# quantum_PSU_V3_0.net
KiCad netlist of a schematic drawn in EAGLE
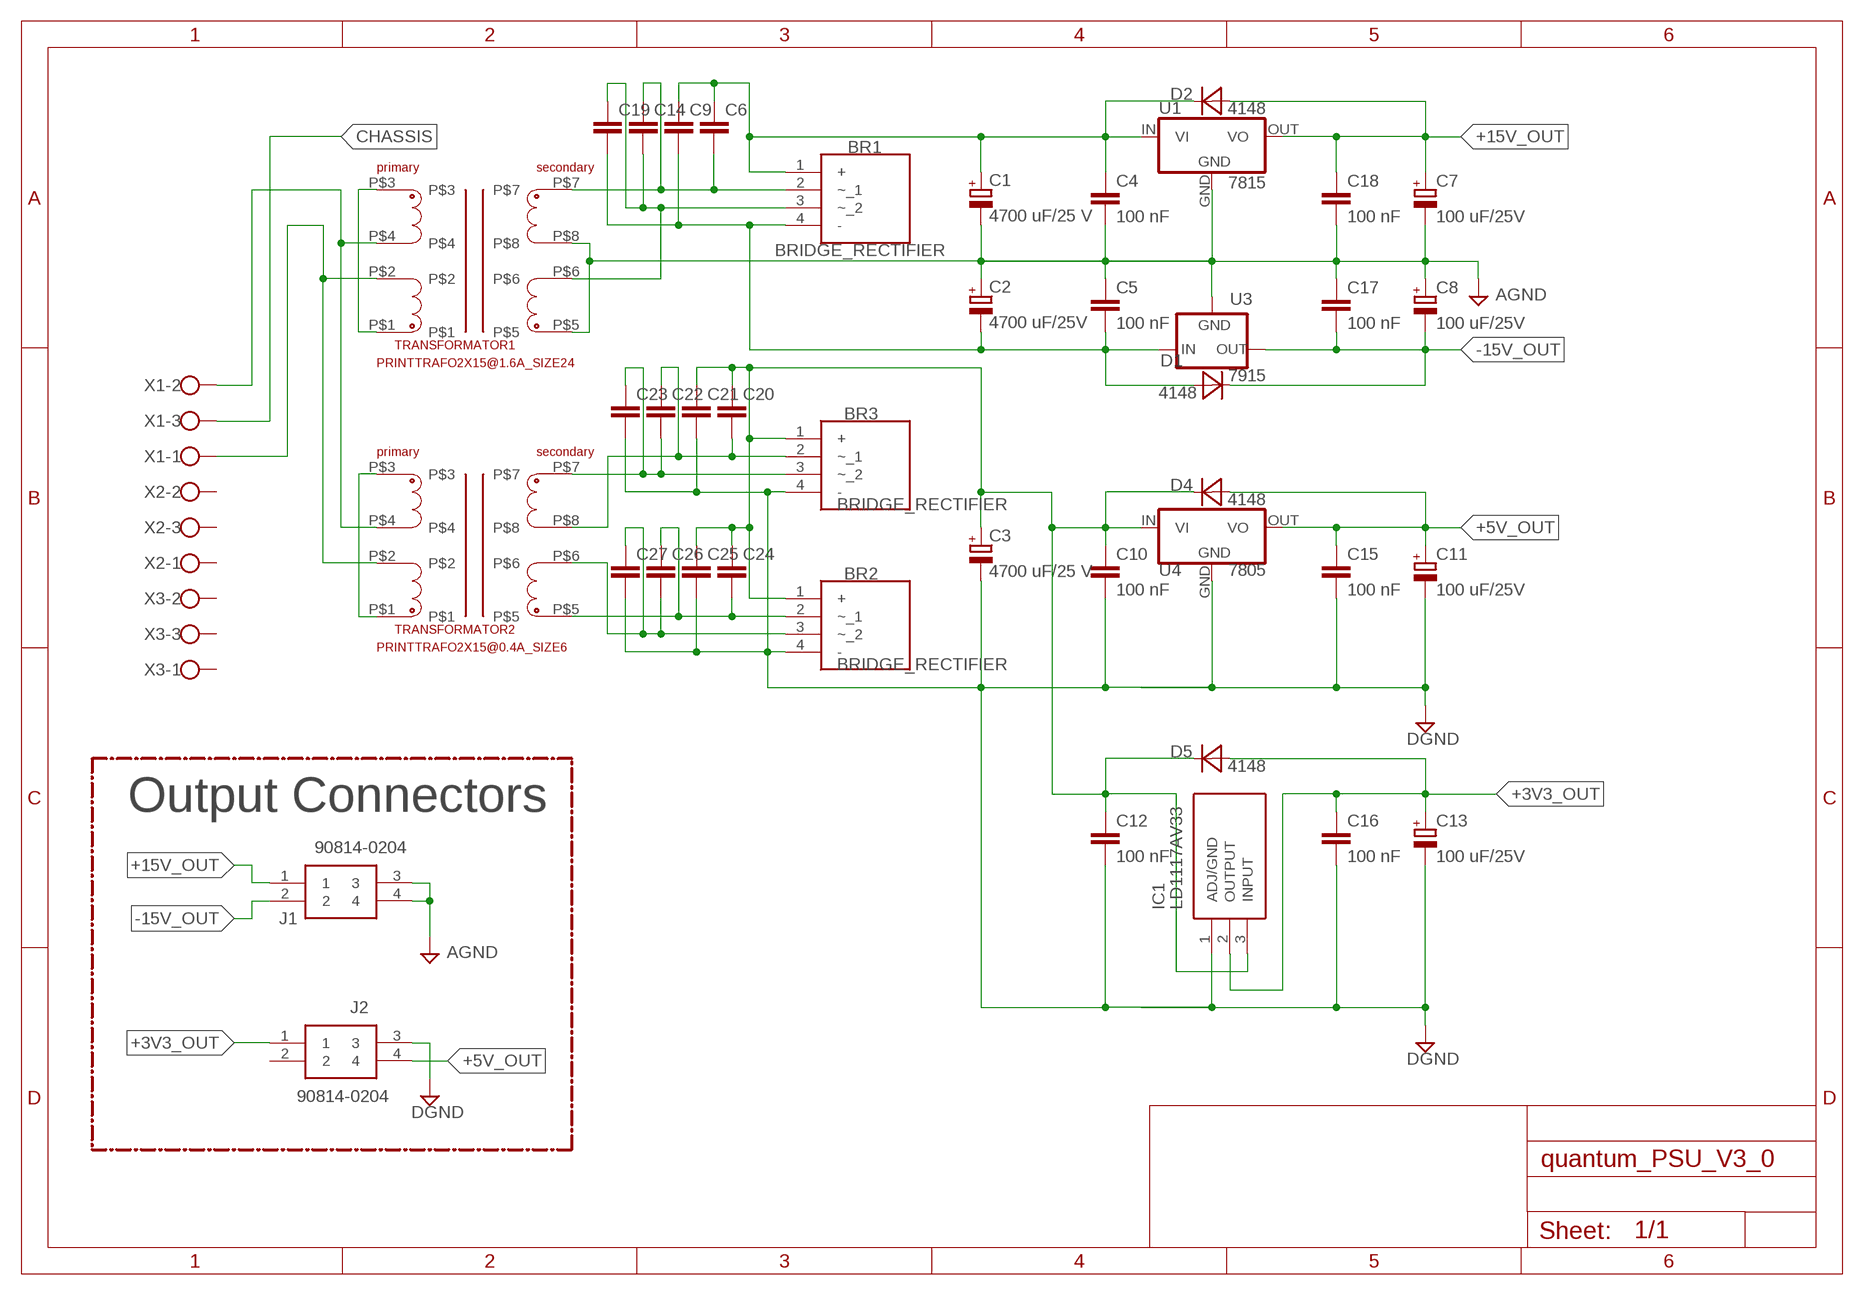
[diagram p0: schematic, sheet 1]

(export (version "E")
  (design (tool "Eeschema 10.0.6"))
  (components
    (comp (ref "BR1")
      (value "BRIDGE_RECTIFIER")
      (footprint "eagle-import:KBP308G")
      (fields
        (field (name "MANUFACTURER_PART_NUMBER") "KBP308G")
        (field (name "MOUSER_PART_NUMBER") "621-KBP308G")
      )
      (libsource (lib "eagle-import") (part "BRIDGE_RECTIFIER"))
    )
    (comp (ref "BR2")
      (value "BRIDGE_RECTIFIER")
      (footprint "eagle-import:KBP308G")
      (fields
        (field (name "MANUFACTURER_PART_NUMBER") "KBP308G")
        (field (name "MOUSER_PART_NUMBER") "621-KBP308G")
      )
      (libsource (lib "eagle-import") (part "BRIDGE_RECTIFIER"))
    )
    (comp (ref "BR3")
      (value "BRIDGE_RECTIFIER")
      (footprint "eagle-import:KBP308G")
      (fields
        (field (name "MANUFACTURER_PART_NUMBER") "KBP308G")
        (field (name "MOUSER_PART_NUMBER") "621-KBP308G")
      )
      (libsource (lib "eagle-import") (part "BRIDGE_RECTIFIER"))
    )
    (comp (ref "C1")
      (value "4700 uF/25 V")
      (footprint "eagle-import:ELECTROLYTIC_16MM")
      (libsource (lib "eagle-import") (part "CAPACITOR_ELECTROLYTIC_16MM-THT"))
    )
    (comp (ref "C2")
      (value "4700 uF/25V")
      (footprint "eagle-import:ELECTROLYTIC_16MM")
      (libsource (lib "eagle-import") (part "CAPACITOR_ELECTROLYTIC_16MM-THT"))
    )
    (comp (ref "C3")
      (value "4700 uF/25 V")
      (footprint "eagle-import:ELECTROLYTIC_16MM")
      (libsource (lib "eagle-import") (part "CAPACITOR_ELECTROLYTIC_16MM-THT"))
    )
    (comp (ref "C4")
      (value "100 nF")
      (footprint "eagle-import:C5MM")
      (libsource (lib "eagle-import") (part "CAPACITOR_5MM"))
    )
    (comp (ref "C5")
      (value "100 nF")
      (footprint "eagle-import:C5MM")
      (libsource (lib "eagle-import") (part "CAPACITOR_5MM"))
    )
    (comp (ref "C6")
      (value "CAPACITOR_2.5MM")
      (footprint "eagle-import:C2.5MM")
      (libsource (lib "eagle-import") (part "CAPACITOR_2.5MM"))
    )
    (comp (ref "C7")
      (value "100 uF/25V")
      (footprint "eagle-import:ELECTROLYTIC_8MM")
      (libsource (lib "eagle-import") (part "CAPACITOR_ELECTROLYTIC_8MM-THT"))
    )
    (comp (ref "C8")
      (value "100 uF/25V")
      (footprint "eagle-import:ELECTROLYTIC_8MM")
      (libsource (lib "eagle-import") (part "CAPACITOR_ELECTROLYTIC_8MM-THT"))
    )
    (comp (ref "C9")
      (value "CAPACITOR_2.5MM")
      (footprint "eagle-import:C2.5MM")
      (libsource (lib "eagle-import") (part "CAPACITOR_2.5MM"))
    )
    (comp (ref "C10")
      (value "100 nF")
      (footprint "eagle-import:C5MM")
      (libsource (lib "eagle-import") (part "CAPACITOR_5MM"))
    )
    (comp (ref "C11")
      (value "100 uF/25V")
      (footprint "eagle-import:ELECTROLYTIC_8MM")
      (libsource (lib "eagle-import") (part "CAPACITOR_ELECTROLYTIC_8MM-THT"))
    )
    (comp (ref "C12")
      (value "100 nF")
      (footprint "eagle-import:C5MM")
      (libsource (lib "eagle-import") (part "CAPACITOR_5MM"))
    )
    (comp (ref "C13")
      (value "100 uF/25V")
      (footprint "eagle-import:ELECTROLYTIC_8MM")
      (libsource (lib "eagle-import") (part "CAPACITOR_ELECTROLYTIC_8MM-THT"))
    )
    (comp (ref "C14")
      (value "CAPACITOR_2.5MM")
      (footprint "eagle-import:C2.5MM")
      (libsource (lib "eagle-import") (part "CAPACITOR_2.5MM"))
    )
    (comp (ref "C15")
      (value "100 nF")
      (footprint "eagle-import:C5MM")
      (libsource (lib "eagle-import") (part "CAPACITOR_5MM"))
    )
    (comp (ref "C16")
      (value "100 nF")
      (footprint "eagle-import:C5MM")
      (libsource (lib "eagle-import") (part "CAPACITOR_5MM"))
    )
    (comp (ref "C17")
      (value "100 nF")
      (footprint "eagle-import:C5MM")
      (libsource (lib "eagle-import") (part "CAPACITOR_5MM"))
    )
    (comp (ref "C18")
      (value "100 nF")
      (footprint "eagle-import:C5MM")
      (libsource (lib "eagle-import") (part "CAPACITOR_5MM"))
    )
    (comp (ref "C19")
      (value "CAPACITOR_2.5MM")
      (footprint "eagle-import:C2.5MM")
      (libsource (lib "eagle-import") (part "CAPACITOR_2.5MM"))
    )
    (comp (ref "C20")
      (value "CAPACITOR_2.5MM")
      (footprint "eagle-import:C2.5MM")
      (libsource (lib "eagle-import") (part "CAPACITOR_2.5MM"))
    )
    (comp (ref "C21")
      (value "CAPACITOR_2.5MM")
      (footprint "eagle-import:C2.5MM")
      (libsource (lib "eagle-import") (part "CAPACITOR_2.5MM"))
    )
    (comp (ref "C22")
      (value "CAPACITOR_2.5MM")
      (footprint "eagle-import:C2.5MM")
      (libsource (lib "eagle-import") (part "CAPACITOR_2.5MM"))
    )
    (comp (ref "C23")
      (value "CAPACITOR_2.5MM")
      (footprint "eagle-import:C2.5MM")
      (libsource (lib "eagle-import") (part "CAPACITOR_2.5MM"))
    )
    (comp (ref "C24")
      (value "CAPACITOR_2.5MM")
      (footprint "eagle-import:C2.5MM")
      (libsource (lib "eagle-import") (part "CAPACITOR_2.5MM"))
    )
    (comp (ref "C25")
      (value "CAPACITOR_2.5MM")
      (footprint "eagle-import:C2.5MM")
      (libsource (lib "eagle-import") (part "CAPACITOR_2.5MM"))
    )
    (comp (ref "C26")
      (value "CAPACITOR_2.5MM")
      (footprint "eagle-import:C2.5MM")
      (libsource (lib "eagle-import") (part "CAPACITOR_2.5MM"))
    )
    (comp (ref "C27")
      (value "CAPACITOR_2.5MM")
      (footprint "eagle-import:C2.5MM")
      (libsource (lib "eagle-import") (part "CAPACITOR_2.5MM"))
    )
    (comp (ref "D1")
      (value "4148")
      (footprint "eagle-import:DIODE_THT_STANDING")
      (fields (field (name "MOUSER_PART_NUMBER") "..."))
      (libsource (lib "eagle-import") (part "DIODE_4148_THT"))
    )
    (comp (ref "D2")
      (value "4148")
      (footprint "eagle-import:DIODE_THT_STANDING")
      (fields (field (name "MOUSER_PART_NUMBER") "..."))
      (libsource (lib "eagle-import") (part "DIODE_4148_THT"))
    )
    (comp (ref "D4")
      (value "4148")
      (footprint "eagle-import:DIODE_THT_STANDING")
      (fields (field (name "MOUSER_PART_NUMBER") "..."))
      (libsource (lib "eagle-import") (part "DIODE_4148_THT"))
    )
    (comp (ref "D5")
      (value "4148")
      (footprint "eagle-import:DIODE_THT_STANDING")
      (fields (field (name "MOUSER_PART_NUMBER") "..."))
      (libsource (lib "eagle-import") (part "DIODE_4148_THT"))
    )
    (comp (ref "IC1")
      (value "LD1117AV33")
      (footprint "eagle-import:TO255P460X1020X2008-3P")
      (fields (field (name "MOUSER_PART_NUMBER") "511-LD1117AV33"))
      (libsource (lib "eagle-import") (part "LD1117AV33"))
    )
    (comp (ref "J1")
      (value "90814-0204")
      (footprint "eagle-import:MOLEX_90814-0204")
      (fields (field (name "MOUSER_PART_NUMBER") "538-90814-0204"))
      (libsource (lib "eagle-import") (part "90814-0204"))
    )
    (comp (ref "J2")
      (value "90814-0204")
      (footprint "eagle-import:MOLEX_90814-0204")
      (fields (field (name "MOUSER_PART_NUMBER") "538-90814-0204"))
      (libsource (lib "eagle-import") (part "90814-0204"))
    )
    (comp (ref "TRANSFORMATOR1")
      (value "PRINTTRAFO2X15@1.6A_SIZE24")
      (footprint "eagle-import:LP_SIZE_24")
      (fields (field (name "MOUSER_PART_NUMBER") "530-LP-30-800"))
      (libsource (lib "eagle-import") (part "PRINTTRAFO_SIZE242X15@1.6A"))
    )
    (comp (ref "TRANSFORMATOR2")
      (value "PRINTTRAFO2X15@0.4A_SIZE6")
      (footprint "eagle-import:LP_SIZE_6")
      (fields (field (name "MOUSER_PART_NUMBER") "530-LP-30-200"))
      (libsource (lib "eagle-import") (part "PRINTTRAFO_SIZE62X15@0.4A"))
    )
    (comp (ref "U1")
      (value "7815")
      (footprint "eagle-import:78XXS_")
      (libsource (lib "eagle-import") (part "78_THT"))
    )
    (comp (ref "U3")
      (value "7915")
      (footprint "eagle-import:79XXS")
      (libsource (lib "eagle-import") (part "79_THT"))
    )
    (comp (ref "U4")
      (value "7805")
      (footprint "eagle-import:78XXS_")
      (libsource (lib "eagle-import") (part "78_THT"))
    )
    (comp (ref "X1")
      (value "CONNECTOR_3POL")
      (footprint "eagle-import:W237-103")
      (libsource (lib "eagle-import") (part "CONNECTOR_3POL"))
    )
    (comp (ref "X2")
      (value "CONNECTOR_3POL")
      (footprint "eagle-import:W237-103")
      (libsource (lib "eagle-import") (part "CONNECTOR_3POL"))
    )
    (comp (ref "X3")
      (value "CONNECTOR_3POL")
      (footprint "eagle-import:W237-103")
      (libsource (lib "eagle-import") (part "CONNECTOR_3POL"))
    )
  )
  (nets
    (net (code "1") (name "+3V3_OUT") (class "Default")
      (node (ref "C13") (pin "+") (pinfunction "+_+") (pintype "passive"))
      (node (ref "C16") (pin "1") (pinfunction "1_1") (pintype "passive"))
      (node (ref "D5") (pin "A") (pinfunction "A_A") (pintype "passive"))
      (node (ref "IC1") (pin "2") (pinfunction "OUTPUT_2") (pintype "bidirectional"))
      (node (ref "J2") (pin "1") (pinfunction "1_1") (pintype "bidirectional"))
    )
    (net (code "2") (name "+5V_OUT") (class "Default")
      (node (ref "C11") (pin "+") (pinfunction "+_+") (pintype "passive"))
      (node (ref "C15") (pin "1") (pinfunction "1_1") (pintype "passive"))
      (node (ref "D4") (pin "A") (pinfunction "A_A") (pintype "passive"))
      (node (ref "J2") (pin "4") (pinfunction "4_4") (pintype "bidirectional"))
      (node (ref "U4") (pin "OUT") (pinfunction "VO_OUT") (pintype "passive"))
    )
    (net (code "3") (name "+15V_OUT") (class "Default")
      (node (ref "C18") (pin "1") (pinfunction "1_1") (pintype "passive"))
      (node (ref "C7") (pin "+") (pinfunction "+_+") (pintype "passive"))
      (node (ref "D2") (pin "A") (pinfunction "A_A") (pintype "passive"))
      (node (ref "J1") (pin "1") (pinfunction "1_1") (pintype "bidirectional"))
      (node (ref "U1") (pin "OUT") (pinfunction "VO_OUT") (pintype "passive"))
    )
    (net (code "4") (name "-15V_OUT") (class "Default")
      (node (ref "C17") (pin "2") (pinfunction "2_2") (pintype "passive"))
      (node (ref "C8") (pin "-") (pinfunction "-_-") (pintype "passive"))
      (node (ref "D1") (pin "C") (pinfunction "C_C") (pintype "passive"))
      (node (ref "J1") (pin "2") (pinfunction "2_2") (pintype "bidirectional"))
      (node (ref "U3") (pin "OUT") (pinfunction "OUT_OUT") (pintype "passive"))
    )
    (net (code "5") (name "AGND") (class "Default")
      (node (ref "C1") (pin "-") (pinfunction "-_-") (pintype "passive"))
      (node (ref "C17") (pin "1") (pinfunction "1_1") (pintype "passive"))
      (node (ref "C18") (pin "2") (pinfunction "2_2") (pintype "passive"))
      (node (ref "C2") (pin "+") (pinfunction "+_+") (pintype "passive"))
      (node (ref "C4") (pin "2") (pinfunction "2_2") (pintype "passive"))
      (node (ref "C5") (pin "1") (pinfunction "1_1") (pintype "passive"))
      (node (ref "C7") (pin "-") (pinfunction "-_-") (pintype "passive"))
      (node (ref "C8") (pin "+") (pinfunction "+_+") (pintype "passive"))
      (node (ref "J1") (pin "3") (pinfunction "3_3") (pintype "bidirectional"))
      (node (ref "J1") (pin "4") (pinfunction "4_4") (pintype "bidirectional"))
      (node (ref "TRANSFORMATOR1") (pin "P$5") (pinfunction "P$5_P$5") (pintype "bidirectional"))
      (node (ref "TRANSFORMATOR1") (pin "P$8") (pinfunction "P$8_P$8") (pintype "bidirectional"))
      (node (ref "U1") (pin "GND") (pinfunction "GND_GND") (pintype "passive"))
      (node (ref "U3") (pin "GND") (pinfunction "GND_GND") (pintype "input"))
    )
    (net (code "6") (name "CHASSIS") (class "Default")
      (node (ref "X1") (pin "3") (pinfunction "KL_3") (pintype "passive"))
    )
    (net (code "7") (name "DGND") (class "Default")
      (node (ref "BR2") (pin "4") (pinfunction "-_4") (pintype "bidirectional"))
      (node (ref "BR3") (pin "4") (pinfunction "-_4") (pintype "bidirectional"))
      (node (ref "C10") (pin "2") (pinfunction "2_2") (pintype "passive"))
      (node (ref "C11") (pin "-") (pinfunction "-_-") (pintype "passive"))
      (node (ref "C12") (pin "2") (pinfunction "2_2") (pintype "passive"))
      (node (ref "C13") (pin "-") (pinfunction "-_-") (pintype "passive"))
      (node (ref "C15") (pin "2") (pinfunction "2_2") (pintype "passive"))
      (node (ref "C16") (pin "2") (pinfunction "2_2") (pintype "passive"))
      (node (ref "C21") (pin "2") (pinfunction "2_2") (pintype "passive"))
      (node (ref "C23") (pin "2") (pinfunction "2_2") (pintype "passive"))
      (node (ref "C25") (pin "2") (pinfunction "2_2") (pintype "passive"))
      (node (ref "C27") (pin "2") (pinfunction "2_2") (pintype "passive"))
      (node (ref "C3") (pin "-") (pinfunction "-_-") (pintype "passive"))
      (node (ref "IC1") (pin "1") (pinfunction "ADJ/GND_1") (pintype "bidirectional"))
      (node (ref "J2") (pin "3") (pinfunction "3_3") (pintype "bidirectional"))
      (node (ref "U4") (pin "GND") (pinfunction "GND_GND") (pintype "passive"))
    )
    (net (code "8") (name "Net-(BR1-+)") (class "Default")
      (node (ref "BR1") (pin "1") (pinfunction "+_1") (pintype "bidirectional"))
      (node (ref "C1") (pin "+") (pinfunction "+_+") (pintype "passive"))
      (node (ref "C4") (pin "1") (pinfunction "1_1") (pintype "passive"))
      (node (ref "C6") (pin "1") (pinfunction "1_1") (pintype "passive"))
      (node (ref "C9") (pin "1") (pinfunction "1_1") (pintype "passive"))
      (node (ref "D2") (pin "C") (pinfunction "C_C") (pintype "passive"))
      (node (ref "U1") (pin "IN") (pinfunction "VI_IN") (pintype "input"))
    )
    (net (code "9") (name "Net-(BR1--)") (class "Default")
      (node (ref "BR1") (pin "4") (pinfunction "-_4") (pintype "bidirectional"))
      (node (ref "C19") (pin "2") (pinfunction "2_2") (pintype "passive"))
      (node (ref "C2") (pin "-") (pinfunction "-_-") (pintype "passive"))
      (node (ref "C5") (pin "2") (pinfunction "2_2") (pintype "passive"))
      (node (ref "C9") (pin "2") (pinfunction "2_2") (pintype "passive"))
      (node (ref "D1") (pin "A") (pinfunction "A_A") (pintype "passive"))
      (node (ref "U3") (pin "IN") (pinfunction "IN_IN") (pintype "input"))
    )
    (net (code "10") (name "Net-(BR1-~{_1})") (class "Default")
      (node (ref "BR1") (pin "2") (pinfunction "~{_1}_2") (pintype "bidirectional"))
      (node (ref "C14") (pin "1") (pinfunction "1_1") (pintype "passive"))
      (node (ref "C6") (pin "2") (pinfunction "2_2") (pintype "passive"))
      (node (ref "TRANSFORMATOR1") (pin "P$7") (pinfunction "P$7_P$7") (pintype "bidirectional"))
    )
    (net (code "11") (name "Net-(BR1-~{_2})") (class "Default")
      (node (ref "BR1") (pin "3") (pinfunction "~{_2}_3") (pintype "bidirectional"))
      (node (ref "C14") (pin "2") (pinfunction "2_2") (pintype "passive"))
      (node (ref "C19") (pin "1") (pinfunction "1_1") (pintype "passive"))
      (node (ref "TRANSFORMATOR1") (pin "P$6") (pinfunction "P$6_P$6") (pintype "bidirectional"))
    )
    (net (code "12") (name "Net-(BR2-+)") (class "Default")
      (node (ref "BR2") (pin "1") (pinfunction "+_1") (pintype "bidirectional"))
      (node (ref "BR3") (pin "1") (pinfunction "+_1") (pintype "bidirectional"))
      (node (ref "C10") (pin "1") (pinfunction "1_1") (pintype "passive"))
      (node (ref "C12") (pin "1") (pinfunction "1_1") (pintype "passive"))
      (node (ref "C20") (pin "1") (pinfunction "1_1") (pintype "passive"))
      (node (ref "C21") (pin "1") (pinfunction "1_1") (pintype "passive"))
      (node (ref "C24") (pin "1") (pinfunction "1_1") (pintype "passive"))
      (node (ref "C25") (pin "1") (pinfunction "1_1") (pintype "passive"))
      (node (ref "C3") (pin "+") (pinfunction "+_+") (pintype "passive"))
      (node (ref "D4") (pin "C") (pinfunction "C_C") (pintype "passive"))
      (node (ref "D5") (pin "C") (pinfunction "C_C") (pintype "passive"))
      (node (ref "IC1") (pin "3") (pinfunction "INPUT_3") (pintype "bidirectional"))
      (node (ref "U4") (pin "IN") (pinfunction "VI_IN") (pintype "input"))
    )
    (net (code "13") (name "Net-(BR2-~{_1})") (class "Default")
      (node (ref "BR2") (pin "2") (pinfunction "~{_1}_2") (pintype "bidirectional"))
      (node (ref "C24") (pin "2") (pinfunction "2_2") (pintype "passive"))
      (node (ref "C26") (pin "1") (pinfunction "1_1") (pintype "passive"))
      (node (ref "TRANSFORMATOR2") (pin "P$5") (pinfunction "P$5_P$5") (pintype "bidirectional"))
    )
    (net (code "14") (name "Net-(BR2-~{_2})") (class "Default")
      (node (ref "BR2") (pin "3") (pinfunction "~{_2}_3") (pintype "bidirectional"))
      (node (ref "C26") (pin "2") (pinfunction "2_2") (pintype "passive"))
      (node (ref "C27") (pin "1") (pinfunction "1_1") (pintype "passive"))
      (node (ref "TRANSFORMATOR2") (pin "P$6") (pinfunction "P$6_P$6") (pintype "bidirectional"))
    )
    (net (code "15") (name "Net-(BR3-~{_1})") (class "Default")
      (node (ref "BR3") (pin "2") (pinfunction "~{_1}_2") (pintype "bidirectional"))
      (node (ref "C20") (pin "2") (pinfunction "2_2") (pintype "passive"))
      (node (ref "C22") (pin "1") (pinfunction "1_1") (pintype "passive"))
      (node (ref "TRANSFORMATOR2") (pin "P$8") (pinfunction "P$8_P$8") (pintype "bidirectional"))
    )
    (net (code "16") (name "Net-(BR3-~{_2})") (class "Default")
      (node (ref "BR3") (pin "3") (pinfunction "~{_2}_3") (pintype "bidirectional"))
      (node (ref "C22") (pin "2") (pinfunction "2_2") (pintype "passive"))
      (node (ref "C23") (pin "1") (pinfunction "1_1") (pintype "passive"))
      (node (ref "TRANSFORMATOR2") (pin "P$7") (pinfunction "P$7_P$7") (pintype "bidirectional"))
    )
    (net (code "17") (name "Net-(TRANSFORMATOR1-PadP$1)") (class "Default")
      (node (ref "TRANSFORMATOR1") (pin "P$1") (pinfunction "P$1_P$1") (pintype "bidirectional"))
      (node (ref "TRANSFORMATOR1") (pin "P$3") (pinfunction "P$3_P$3") (pintype "bidirectional"))
    )
    (net (code "18") (name "Net-(TRANSFORMATOR2-PadP$1)") (class "Default")
      (node (ref "TRANSFORMATOR2") (pin "P$1") (pinfunction "P$1_P$1") (pintype "bidirectional"))
      (node (ref "TRANSFORMATOR2") (pin "P$3") (pinfunction "P$3_P$3") (pintype "bidirectional"))
    )
    (net (code "19") (name "Net-(X1A-KL)") (class "Default")
      (node (ref "TRANSFORMATOR1") (pin "P$2") (pinfunction "P$2_P$2") (pintype "bidirectional"))
      (node (ref "TRANSFORMATOR2") (pin "P$2") (pinfunction "P$2_P$2") (pintype "bidirectional"))
      (node (ref "X1") (pin "1") (pinfunction "KL_1") (pintype "passive"))
    )
    (net (code "20") (name "Net-(X1B-KL)") (class "Default")
      (node (ref "TRANSFORMATOR1") (pin "P$4") (pinfunction "P$4_P$4") (pintype "bidirectional"))
      (node (ref "TRANSFORMATOR2") (pin "P$4") (pinfunction "P$4_P$4") (pintype "bidirectional"))
      (node (ref "X1") (pin "2") (pinfunction "KL_2") (pintype "passive"))
    )
    (net (code "21") (name "unconnected-(J2-Pad2)") (class "Default")
      (node (ref "J2") (pin "2") (pinfunction "2_2") (pintype "bidirectional"))
    )
    (net (code "22") (name "unconnected-(X2A-KL-Pad1)") (class "Default")
      (node (ref "X2") (pin "1") (pinfunction "KL_1") (pintype "passive"))
    )
    (net (code "23") (name "unconnected-(X2B-KL-Pad2)") (class "Default")
      (node (ref "X2") (pin "2") (pinfunction "KL_2") (pintype "passive"))
    )
    (net (code "24") (name "unconnected-(X2C-KL-Pad3)") (class "Default")
      (node (ref "X2") (pin "3") (pinfunction "KL_3") (pintype "passive"))
    )
    (net (code "25") (name "unconnected-(X3A-KL-Pad1)") (class "Default")
      (node (ref "X3") (pin "1") (pinfunction "KL_1") (pintype "passive"))
    )
    (net (code "26") (name "unconnected-(X3B-KL-Pad2)") (class "Default")
      (node (ref "X3") (pin "2") (pinfunction "KL_2") (pintype "passive"))
    )
    (net (code "27") (name "unconnected-(X3C-KL-Pad3)") (class "Default")
      (node (ref "X3") (pin "3") (pinfunction "KL_3") (pintype "passive"))
    )
  )
)
